# 11-DSP_PROCESSOR_1-OF-3.net
KiCad netlist of a schematic drawn in Altium Designer
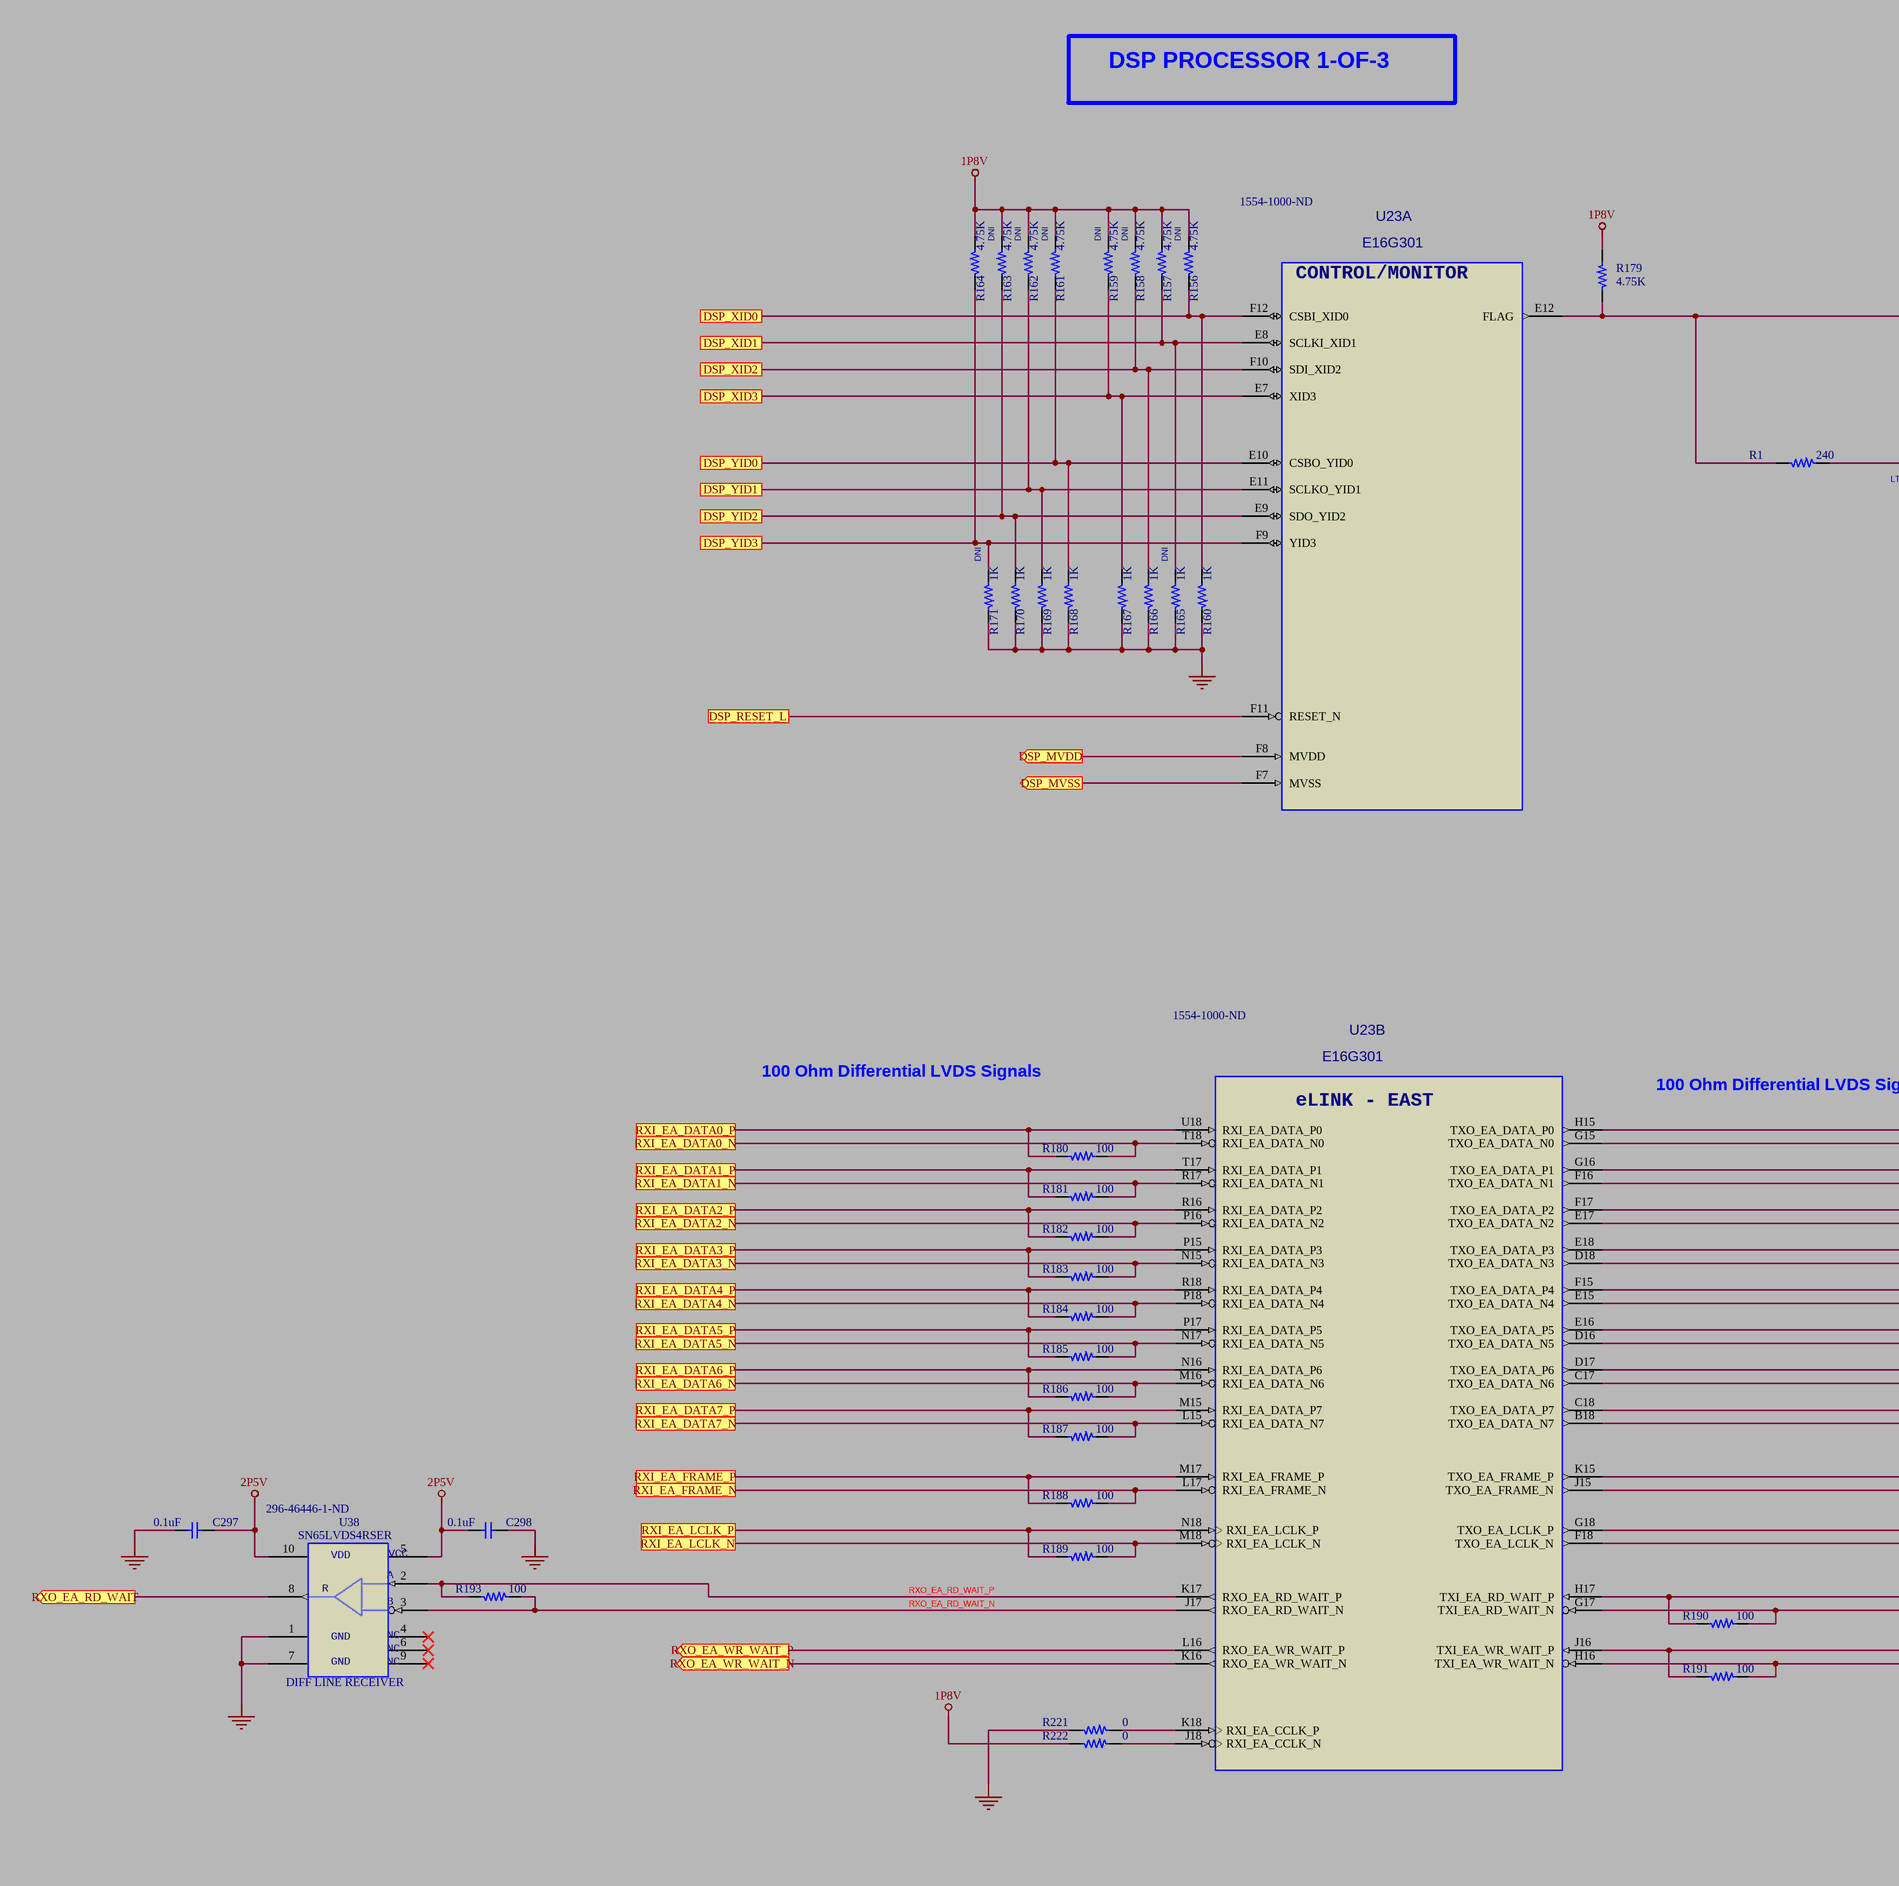
[diagram p0: 11-DSP PROCESSOR 1-OF-3.SchDoc, left]
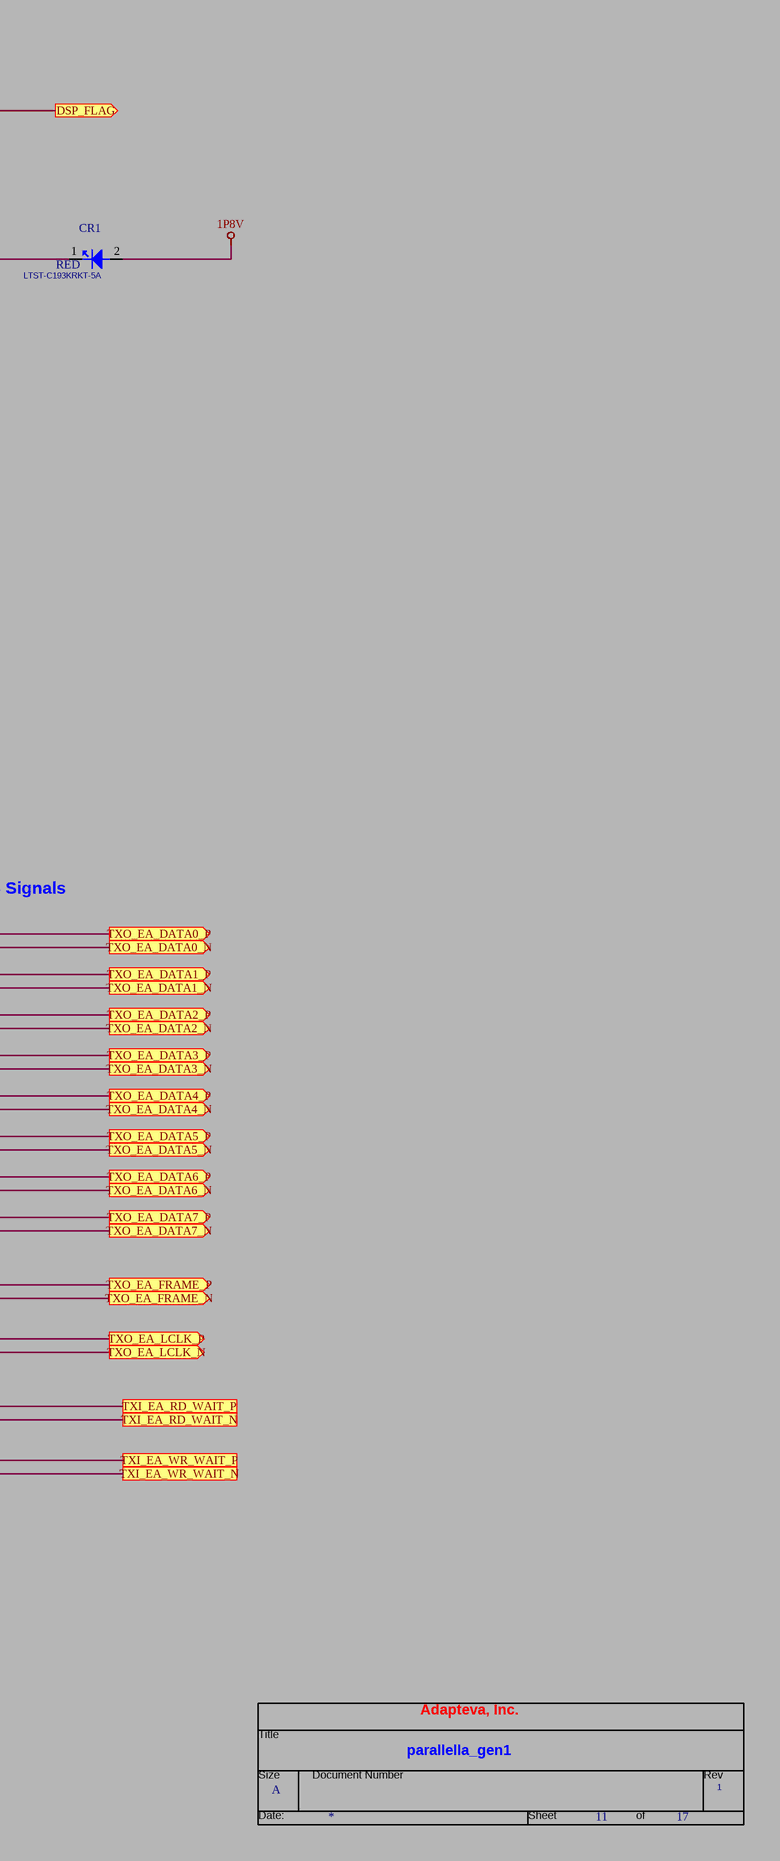
[diagram p1: 11-DSP PROCESSOR 1-OF-3.SchDoc, right]

(export (version "E")
  (design (tool "Eeschema 10.0.6"))
  (components
    (comp (ref "C297")
      (value "0.1uF")
      (footprint "C0402")
      (description "CAP, 0402, 0.1UF, X5R, 35V")
      (fields (field (name "MFG PART NO") "GMK105BJ104KV-F") (field (name "MFG") "TAIYO YUDEN"))
      (libsource (lib "*") (part "CAP0402_0P1UF_X5R_35V"))
    )
    (comp (ref "C298")
      (value "0.1uF")
      (footprint "C0402")
      (description "CAP, 0402, 0.1UF, X5R, 35V")
      (fields (field (name "MFG PART NO") "GMK105BJ104KV-F") (field (name "MFG") "TAIYO YUDEN"))
      (libsource (lib "*") (part "CAP0402_0P1UF_X5R_35V"))
    )
    (comp (ref "CR1")
      (value "RED")
      (footprint "LED_0603")
      (description "LED, 0603, 5MA, SMT, RED")
      (fields
        (field (name "VOLTAGE") "2V")
        (field (name "MFG") "LITE-ON INC")
        (field (name "VENDOR PN") "LTST-C193KRKT-5A")
      )
      (libsource (lib "*") (part "LED_0603_5MA_RED"))
    )
    (comp (ref "R1")
      (value "240")
      (footprint "R0402")
      (description "RES, 0402, 240, 1%")
      (fields (field (name "MFG") "VISHAY") (field (name "MFG PART NO") "CRCW0402240RFKED"))
      (libsource (lib "*") (part "RES0402_240"))
    )
    (comp (ref "R156")
      (value "4.75K")
      (footprint "R0402")
      (description "RES, 0402, 4.75K, 1%")
      (fields
        (field (name "MFG") "VISHAY")
        (field (name "MFG PART NO") "CRCW04024K75FKED")
        (field (name "INSTALL") "DNI")
      )
      (libsource (lib "*") (part "RES0402_4K75"))
    )
    (comp (ref "R157")
      (value "4.75K")
      (footprint "R0402")
      (description "RES, 0402, 4.75K, 1%")
      (fields (field (name "MFG") "VISHAY") (field (name "MFG PART NO") "CRCW04024K75FKED"))
      (libsource (lib "*") (part "RES0402_4K75"))
    )
    (comp (ref "R158")
      (value "4.75K")
      (footprint "R0402")
      (description "RES, 0402, 4.75K, 1%")
      (fields
        (field (name "MFG") "VISHAY")
        (field (name "MFG PART NO") "CRCW04024K75FKED")
        (field (name "INSTALL") "DNI")
      )
      (libsource (lib "*") (part "RES0402_4K75"))
    )
    (comp (ref "R159")
      (value "4.75K")
      (footprint "R0402")
      (description "RES, 0402, 4.75K, 1%")
      (fields
        (field (name "MFG") "VISHAY")
        (field (name "MFG PART NO") "CRCW04024K75FKED")
        (field (name "INSTALL") "DNI")
      )
      (libsource (lib "*") (part "RES0402_4K75"))
    )
    (comp (ref "R160")
      (value "1K")
      (footprint "R0402")
      (description "RES, 0402, 1K")
      (fields (field (name "MFG") "VISHAY") (field (name "MFG PART NO") "CRCW04021K00FKED"))
      (libsource (lib "*") (part "RES0402_1K"))
    )
    (comp (ref "R161")
      (value "4.75K")
      (footprint "R0402")
      (description "RES, 0402, 4.75K, 1%")
      (fields
        (field (name "MFG") "VISHAY")
        (field (name "MFG PART NO") "CRCW04024K75FKED")
        (field (name "INSTALL") "DNI")
      )
      (libsource (lib "*") (part "RES0402_4K75"))
    )
    (comp (ref "R162")
      (value "4.75K")
      (footprint "R0402")
      (description "RES, 0402, 4.75K, 1%")
      (fields
        (field (name "MFG") "VISHAY")
        (field (name "MFG PART NO") "CRCW04024K75FKED")
        (field (name "INSTALL") "DNI")
      )
      (libsource (lib "*") (part "RES0402_4K75"))
    )
    (comp (ref "R163")
      (value "4.75K")
      (footprint "R0402")
      (description "RES, 0402, 4.75K, 1%")
      (fields
        (field (name "MFG") "VISHAY")
        (field (name "MFG PART NO") "CRCW04024K75FKED")
        (field (name "INSTALL") "DNI")
      )
      (libsource (lib "*") (part "RES0402_4K75"))
    )
    (comp (ref "R164")
      (value "4.75K")
      (footprint "R0402")
      (description "RES, 0402, 4.75K, 1%")
      (fields (field (name "MFG") "VISHAY") (field (name "MFG PART NO") "CRCW04024K75FKED"))
      (libsource (lib "*") (part "RES0402_4K75"))
    )
    (comp (ref "R165")
      (value "1K")
      (footprint "R0402")
      (description "RES, 0402, 1K")
      (fields
        (field (name "MFG") "VISHAY")
        (field (name "MFG PART NO") "CRCW04021K00FKED")
        (field (name "INSTALL") "DNI")
      )
      (libsource (lib "*") (part "RES0402_1K"))
    )
    (comp (ref "R166")
      (value "1K")
      (footprint "R0402")
      (description "RES, 0402, 1K")
      (fields (field (name "MFG") "VISHAY") (field (name "MFG PART NO") "CRCW04021K00FKED"))
      (libsource (lib "*") (part "RES0402_1K"))
    )
    (comp (ref "R167")
      (value "1K")
      (footprint "R0402")
      (description "RES, 0402, 1K")
      (fields (field (name "MFG") "VISHAY") (field (name "MFG PART NO") "CRCW04021K00FKED"))
      (libsource (lib "*") (part "RES0402_1K"))
    )
    (comp (ref "R168")
      (value "1K")
      (footprint "R0402")
      (description "RES, 0402, 1K")
      (fields (field (name "MFG") "VISHAY") (field (name "MFG PART NO") "CRCW04021K00FKED"))
      (libsource (lib "*") (part "RES0402_1K"))
    )
    (comp (ref "R169")
      (value "1K")
      (footprint "R0402")
      (description "RES, 0402, 1K")
      (fields (field (name "MFG") "VISHAY") (field (name "MFG PART NO") "CRCW04021K00FKED"))
      (libsource (lib "*") (part "RES0402_1K"))
    )
    (comp (ref "R170")
      (value "1K")
      (footprint "R0402")
      (description "RES, 0402, 1K")
      (fields (field (name "MFG") "VISHAY") (field (name "MFG PART NO") "CRCW04021K00FKED"))
      (libsource (lib "*") (part "RES0402_1K"))
    )
    (comp (ref "R171")
      (value "1K")
      (footprint "R0402")
      (description "RES, 0402, 1K")
      (fields
        (field (name "MFG") "VISHAY")
        (field (name "MFG PART NO") "CRCW04021K00FKED")
        (field (name "INSTALL") "DNI")
      )
      (libsource (lib "*") (part "RES0402_1K"))
    )
    (comp (ref "R179")
      (value "4.75K")
      (footprint "R0402")
      (description "RES, 0402, 4.75K, 1%")
      (fields (field (name "MFG") "VISHAY") (field (name "MFG PART NO") "CRCW04024K75FKED"))
      (libsource (lib "*") (part "RES0402_4K75"))
    )
    (comp (ref "R180")
      (value "100")
      (footprint "R0402")
      (description "RES, 0402, 100, 1%")
      (fields (field (name "MFG PART NO") "CRCW0402100RFKED") (field (name "MFG") "VISHAY"))
      (libsource (lib "*") (part "RES0402_100"))
    )
    (comp (ref "R181")
      (value "100")
      (footprint "R0402")
      (description "RES, 0402, 100, 1%")
      (fields (field (name "MFG PART NO") "CRCW0402100RFKED") (field (name "MFG") "VISHAY"))
      (libsource (lib "*") (part "RES0402_100"))
    )
    (comp (ref "R182")
      (value "100")
      (footprint "R0402")
      (description "RES, 0402, 100, 1%")
      (fields (field (name "MFG PART NO") "CRCW0402100RFKED") (field (name "MFG") "VISHAY"))
      (libsource (lib "*") (part "RES0402_100"))
    )
    (comp (ref "R183")
      (value "100")
      (footprint "R0402")
      (description "RES, 0402, 100, 1%")
      (fields (field (name "MFG PART NO") "CRCW0402100RFKED") (field (name "MFG") "VISHAY"))
      (libsource (lib "*") (part "RES0402_100"))
    )
    (comp (ref "R184")
      (value "100")
      (footprint "R0402")
      (description "RES, 0402, 100, 1%")
      (fields (field (name "MFG PART NO") "CRCW0402100RFKED") (field (name "MFG") "VISHAY"))
      (libsource (lib "*") (part "RES0402_100"))
    )
    (comp (ref "R185")
      (value "100")
      (footprint "R0402")
      (description "RES, 0402, 100, 1%")
      (fields (field (name "MFG PART NO") "CRCW0402100RFKED") (field (name "MFG") "VISHAY"))
      (libsource (lib "*") (part "RES0402_100"))
    )
    (comp (ref "R186")
      (value "100")
      (footprint "R0402")
      (description "RES, 0402, 100, 1%")
      (fields (field (name "MFG PART NO") "CRCW0402100RFKED") (field (name "MFG") "VISHAY"))
      (libsource (lib "*") (part "RES0402_100"))
    )
    (comp (ref "R187")
      (value "100")
      (footprint "R0402")
      (description "RES, 0402, 100, 1%")
      (fields (field (name "MFG PART NO") "CRCW0402100RFKED") (field (name "MFG") "VISHAY"))
      (libsource (lib "*") (part "RES0402_100"))
    )
    (comp (ref "R188")
      (value "100")
      (footprint "R0402")
      (description "RES, 0402, 100, 1%")
      (fields (field (name "MFG PART NO") "CRCW0402100RFKED") (field (name "MFG") "VISHAY"))
      (libsource (lib "*") (part "RES0402_100"))
    )
    (comp (ref "R189")
      (value "100")
      (footprint "R0402")
      (description "RES, 0402, 100, 1%")
      (fields (field (name "MFG PART NO") "CRCW0402100RFKED") (field (name "MFG") "VISHAY"))
      (libsource (lib "*") (part "RES0402_100"))
    )
    (comp (ref "R190")
      (value "100")
      (footprint "R0402")
      (description "RES, 0402, 100, 1%")
      (fields (field (name "MFG PART NO") "CRCW0402100RFKED") (field (name "MFG") "VISHAY"))
      (libsource (lib "*") (part "RES0402_100"))
    )
    (comp (ref "R191")
      (value "100")
      (footprint "R0402")
      (description "RES, 0402, 100, 1%")
      (fields (field (name "MFG PART NO") "CRCW0402100RFKED") (field (name "MFG") "VISHAY"))
      (libsource (lib "*") (part "RES0402_100"))
    )
    (comp (ref "R193")
      (value "100")
      (footprint "R0402")
      (description "RES, 0402, 100, 1%")
      (fields (field (name "MFG PART NO") "CRCW0402100RFKED") (field (name "MFG") "VISHAY"))
      (libsource (lib "*") (part "RES0402_100"))
    )
    (comp (ref "R221")
      (value "0")
      (footprint "R0402")
      (description "RES, 0402, 0 OHM, 1%")
      (fields (field (name "MFG") "VISHAY") (field (name "MFG PART NO") "CRCW04020000Z0ED"))
      (libsource (lib "*") (part "RES0402_0"))
    )
    (comp (ref "R222")
      (value "0")
      (footprint "R0402")
      (description "RES, 0402, 0 OHM, 1%")
      (fields (field (name "MFG") "VISHAY") (field (name "MFG PART NO") "CRCW04020000Z0ED"))
      (libsource (lib "*") (part "RES0402_0"))
    )
    (comp (ref "U23")
      (value "16-CORE MICROPROCESSOR")
      (footprint "BGA324_15SQX1P5_P8MMP")
      (description "IC, 16-CORE MICROPROCESSOR, ADAPTEVA, E16G301, BGA324")
      (fields (field (name "VENDOR PN") "E16G301") (field (name "SUPPLIER PART NUMBER 1") "1554-1000-ND"))
      (libsource (lib "*") (part "EPIPHANY_E16G301"))
    )
    (comp (ref "U38")
      (value "DIFF LINE RECEIVER")
      (footprint "QFN-10_1P55X2P05XP6XP5MMP")
      (description "IC, LINE RECEIVER, DIFFERENTIAL LVDS, UFQFN10")
      (fields
        (field (name "VENDOR PN") "SN65LVDS4RSER")
        (field (name "MFG") "TEXAS INSTRUMENTS")
        (field (name "MFG PART NO") "SN65LVDS4RSER")
        (field (name "SUPPLIER PART NUMBER 1") "296-46446-1-ND")
      )
      (libsource (lib "*") (part "SN65LVDS4"))
    )
  )
  (nets
    (net (code "1") (name "/DSP_FLAG") (class "Default")
      (node (ref "R1") (pin "1") (pinfunction "1_1") (pintype "passive"))
      (node (ref "R179") (pin "1") (pinfunction "1_1") (pintype "passive"))
      (node (ref "U23") (pin "E12") (pinfunction "FLAG_E12") (pintype "output"))
    )
    (net (code "2") (name "/DSP_MVDD") (class "Default")
      (node (ref "U23") (pin "F8") (pinfunction "MVDD_F8") (pintype "input"))
    )
    (net (code "3") (name "/DSP_MVSS") (class "Default")
      (node (ref "U23") (pin "F7") (pinfunction "MVSS_F7") (pintype "input"))
    )
    (net (code "4") (name "/DSP_RESET_L") (class "Default")
      (node (ref "U23") (pin "F11") (pinfunction "RESET_N_F11") (pintype "input"))
    )
    (net (code "5") (name "/DSP_XID0") (class "Default")
      (node (ref "R156") (pin "1") (pinfunction "1_1") (pintype "passive"))
      (node (ref "R160") (pin "1") (pinfunction "1_1") (pintype "passive"))
      (node (ref "U23") (pin "F12") (pinfunction "CSBI_XID0_F12") (pintype "bidirectional"))
    )
    (net (code "6") (name "/DSP_XID1") (class "Default")
      (node (ref "R157") (pin "1") (pinfunction "1_1") (pintype "passive"))
      (node (ref "R165") (pin "1") (pinfunction "1_1") (pintype "passive"))
      (node (ref "U23") (pin "E8") (pinfunction "SCLKI_XID1_E8") (pintype "bidirectional"))
    )
    (net (code "7") (name "/DSP_XID2") (class "Default")
      (node (ref "R158") (pin "1") (pinfunction "1_1") (pintype "passive"))
      (node (ref "R166") (pin "1") (pinfunction "1_1") (pintype "passive"))
      (node (ref "U23") (pin "F10") (pinfunction "SDI_XID2_F10") (pintype "bidirectional"))
    )
    (net (code "8") (name "/DSP_XID3") (class "Default")
      (node (ref "R159") (pin "1") (pinfunction "1_1") (pintype "passive"))
      (node (ref "R167") (pin "1") (pinfunction "1_1") (pintype "passive"))
      (node (ref "U23") (pin "E7") (pinfunction "XID3_E7") (pintype "bidirectional"))
    )
    (net (code "9") (name "/DSP_YID0") (class "Default")
      (node (ref "R161") (pin "1") (pinfunction "1_1") (pintype "passive"))
      (node (ref "R168") (pin "1") (pinfunction "1_1") (pintype "passive"))
      (node (ref "U23") (pin "E10") (pinfunction "CSBO_YID0_E10") (pintype "bidirectional"))
    )
    (net (code "10") (name "/DSP_YID1") (class "Default")
      (node (ref "R162") (pin "1") (pinfunction "1_1") (pintype "passive"))
      (node (ref "R169") (pin "1") (pinfunction "1_1") (pintype "passive"))
      (node (ref "U23") (pin "E11") (pinfunction "SCLKO_YID1_E11") (pintype "bidirectional"))
    )
    (net (code "11") (name "/DSP_YID2") (class "Default")
      (node (ref "R163") (pin "1") (pinfunction "1_1") (pintype "passive"))
      (node (ref "R170") (pin "1") (pinfunction "1_1") (pintype "passive"))
      (node (ref "U23") (pin "E9") (pinfunction "SDO_YID2_E9") (pintype "bidirectional"))
    )
    (net (code "12") (name "/DSP_YID3") (class "Default")
      (node (ref "R164") (pin "1") (pinfunction "1_1") (pintype "passive"))
      (node (ref "R171") (pin "1") (pinfunction "1_1") (pintype "passive"))
      (node (ref "U23") (pin "F9") (pinfunction "YID3_F9") (pintype "bidirectional"))
    )
    (net (code "13") (name "/RXI_EA_DATA0_N") (class "Default")
      (node (ref "R180") (pin "2") (pinfunction "2_2") (pintype "passive"))
      (node (ref "U23") (pin "T18") (pinfunction "RXI_EA_DATA_N0_T18") (pintype "input"))
    )
    (net (code "14") (name "/RXI_EA_DATA0_P") (class "Default")
      (node (ref "R180") (pin "1") (pinfunction "1_1") (pintype "passive"))
      (node (ref "U23") (pin "U18") (pinfunction "RXI_EA_DATA_P0_U18") (pintype "input"))
    )
    (net (code "15") (name "/RXI_EA_DATA1_N") (class "Default")
      (node (ref "R181") (pin "2") (pinfunction "2_2") (pintype "passive"))
      (node (ref "U23") (pin "R17") (pinfunction "RXI_EA_DATA_N1_R17") (pintype "input"))
    )
    (net (code "16") (name "/RXI_EA_DATA1_P") (class "Default")
      (node (ref "R181") (pin "1") (pinfunction "1_1") (pintype "passive"))
      (node (ref "U23") (pin "T17") (pinfunction "RXI_EA_DATA_P1_T17") (pintype "input"))
    )
    (net (code "17") (name "/RXI_EA_DATA2_N") (class "Default")
      (node (ref "R182") (pin "2") (pinfunction "2_2") (pintype "passive"))
      (node (ref "U23") (pin "P16") (pinfunction "RXI_EA_DATA_N2_P16") (pintype "input"))
    )
    (net (code "18") (name "/RXI_EA_DATA2_P") (class "Default")
      (node (ref "R182") (pin "1") (pinfunction "1_1") (pintype "passive"))
      (node (ref "U23") (pin "R16") (pinfunction "RXI_EA_DATA_P2_R16") (pintype "input"))
    )
    (net (code "19") (name "/RXI_EA_DATA3_N") (class "Default")
      (node (ref "R183") (pin "2") (pinfunction "2_2") (pintype "passive"))
      (node (ref "U23") (pin "N15") (pinfunction "RXI_EA_DATA_N3_N15") (pintype "input"))
    )
    (net (code "20") (name "/RXI_EA_DATA3_P") (class "Default")
      (node (ref "R183") (pin "1") (pinfunction "1_1") (pintype "passive"))
      (node (ref "U23") (pin "P15") (pinfunction "RXI_EA_DATA_P3_P15") (pintype "input"))
    )
    (net (code "21") (name "/RXI_EA_DATA4_N") (class "Default")
      (node (ref "R184") (pin "2") (pinfunction "2_2") (pintype "passive"))
      (node (ref "U23") (pin "P18") (pinfunction "RXI_EA_DATA_N4_P18") (pintype "input"))
    )
    (net (code "22") (name "/RXI_EA_DATA4_P") (class "Default")
      (node (ref "R184") (pin "1") (pinfunction "1_1") (pintype "passive"))
      (node (ref "U23") (pin "R18") (pinfunction "RXI_EA_DATA_P4_R18") (pintype "input"))
    )
    (net (code "23") (name "/RXI_EA_DATA5_N") (class "Default")
      (node (ref "R185") (pin "2") (pinfunction "2_2") (pintype "passive"))
      (node (ref "U23") (pin "N17") (pinfunction "RXI_EA_DATA_N5_N17") (pintype "input"))
    )
    (net (code "24") (name "/RXI_EA_DATA5_P") (class "Default")
      (node (ref "R185") (pin "1") (pinfunction "1_1") (pintype "passive"))
      (node (ref "U23") (pin "P17") (pinfunction "RXI_EA_DATA_P5_P17") (pintype "input"))
    )
    (net (code "25") (name "/RXI_EA_DATA6_N") (class "Default")
      (node (ref "R186") (pin "2") (pinfunction "2_2") (pintype "passive"))
      (node (ref "U23") (pin "M16") (pinfunction "RXI_EA_DATA_N6_M16") (pintype "input"))
    )
    (net (code "26") (name "/RXI_EA_DATA6_P") (class "Default")
      (node (ref "R186") (pin "1") (pinfunction "1_1") (pintype "passive"))
      (node (ref "U23") (pin "N16") (pinfunction "RXI_EA_DATA_P6_N16") (pintype "input"))
    )
    (net (code "27") (name "/RXI_EA_DATA7_N") (class "Default")
      (node (ref "R187") (pin "2") (pinfunction "2_2") (pintype "passive"))
      (node (ref "U23") (pin "L15") (pinfunction "RXI_EA_DATA_N7_L15") (pintype "input"))
    )
    (net (code "28") (name "/RXI_EA_DATA7_P") (class "Default")
      (node (ref "R187") (pin "1") (pinfunction "1_1") (pintype "passive"))
      (node (ref "U23") (pin "M15") (pinfunction "RXI_EA_DATA_P7_M15") (pintype "input"))
    )
    (net (code "29") (name "/RXI_EA_FRAME_N") (class "Default")
      (node (ref "R188") (pin "2") (pinfunction "2_2") (pintype "passive"))
      (node (ref "U23") (pin "L17") (pinfunction "RXI_EA_FRAME_N_L17") (pintype "input"))
    )
    (net (code "30") (name "/RXI_EA_FRAME_P") (class "Default")
      (node (ref "R188") (pin "1") (pinfunction "1_1") (pintype "passive"))
      (node (ref "U23") (pin "M17") (pinfunction "RXI_EA_FRAME_P_M17") (pintype "input"))
    )
    (net (code "31") (name "/RXI_EA_LCLK_N") (class "Default")
      (node (ref "R189") (pin "2") (pinfunction "2_2") (pintype "passive"))
      (node (ref "U23") (pin "M18") (pinfunction "RXI_EA_LCLK_N_M18") (pintype "input"))
    )
    (net (code "32") (name "/RXI_EA_LCLK_P") (class "Default")
      (node (ref "R189") (pin "1") (pinfunction "1_1") (pintype "passive"))
      (node (ref "U23") (pin "N18") (pinfunction "RXI_EA_LCLK_P_N18") (pintype "input"))
    )
    (net (code "33") (name "/RXO_EA_RD_WAIT") (class "Default")
      (node (ref "U38") (pin "8") (pinfunction "R_8") (pintype "output"))
    )
    (net (code "34") (name "/RXO_EA_RD_WAIT_N") (class "Default")
      (node (ref "R193") (pin "2") (pinfunction "2_2") (pintype "passive"))
      (node (ref "U23") (pin "J17") (pinfunction "RXO_EA_RD_WAIT_N_J17") (pintype "output"))
      (node (ref "U38") (pin "3") (pinfunction "B_3") (pintype "input"))
    )
    (net (code "35") (name "/RXO_EA_RD_WAIT_P") (class "Default")
      (node (ref "R193") (pin "1") (pinfunction "1_1") (pintype "passive"))
      (node (ref "U23") (pin "K17") (pinfunction "RXO_EA_RD_WAIT_P_K17") (pintype "output"))
      (node (ref "U38") (pin "2") (pinfunction "A_2") (pintype "input"))
    )
    (net (code "36") (name "/RXO_EA_WR_WAIT_N") (class "Default")
      (node (ref "U23") (pin "K16") (pinfunction "RXO_EA_WR_WAIT_N_K16") (pintype "output"))
    )
    (net (code "37") (name "/RXO_EA_WR_WAIT_P") (class "Default")
      (node (ref "U23") (pin "L16") (pinfunction "RXO_EA_WR_WAIT_P_L16") (pintype "output"))
    )
    (net (code "38") (name "/TXI_EA_RD_WAIT_N") (class "Default")
      (node (ref "R190") (pin "2") (pinfunction "2_2") (pintype "passive"))
      (node (ref "U23") (pin "G17") (pinfunction "TXI_EA_RD_WAIT_N_G17") (pintype "input"))
    )
    (net (code "39") (name "/TXI_EA_RD_WAIT_P") (class "Default")
      (node (ref "R190") (pin "1") (pinfunction "1_1") (pintype "passive"))
      (node (ref "U23") (pin "H17") (pinfunction "TXI_EA_RD_WAIT_P_H17") (pintype "input"))
    )
    (net (code "40") (name "/TXI_EA_WR_WAIT_N") (class "Default")
      (node (ref "R191") (pin "2") (pinfunction "2_2") (pintype "passive"))
      (node (ref "U23") (pin "H16") (pinfunction "TXI_EA_WR_WAIT_N_H16") (pintype "input"))
    )
    (net (code "41") (name "/TXI_EA_WR_WAIT_P") (class "Default")
      (node (ref "R191") (pin "1") (pinfunction "1_1") (pintype "passive"))
      (node (ref "U23") (pin "J16") (pinfunction "TXI_EA_WR_WAIT_P_J16") (pintype "input"))
    )
    (net (code "42") (name "/TXO_EA_DATA0_N") (class "Default")
      (node (ref "U23") (pin "G15") (pinfunction "TXO_EA_DATA_N0_G15") (pintype "output"))
    )
    (net (code "43") (name "/TXO_EA_DATA0_P") (class "Default")
      (node (ref "U23") (pin "H15") (pinfunction "TXO_EA_DATA_P0_H15") (pintype "output"))
    )
    (net (code "44") (name "/TXO_EA_DATA1_N") (class "Default")
      (node (ref "U23") (pin "F16") (pinfunction "TXO_EA_DATA_N1_F16") (pintype "output"))
    )
    (net (code "45") (name "/TXO_EA_DATA1_P") (class "Default")
      (node (ref "U23") (pin "G16") (pinfunction "TXO_EA_DATA_P1_G16") (pintype "output"))
    )
    (net (code "46") (name "/TXO_EA_DATA2_N") (class "Default")
      (node (ref "U23") (pin "E17") (pinfunction "TXO_EA_DATA_N2_E17") (pintype "output"))
    )
    (net (code "47") (name "/TXO_EA_DATA2_P") (class "Default")
      (node (ref "U23") (pin "F17") (pinfunction "TXO_EA_DATA_P2_F17") (pintype "output"))
    )
    (net (code "48") (name "/TXO_EA_DATA3_N") (class "Default")
      (node (ref "U23") (pin "D18") (pinfunction "TXO_EA_DATA_N3_D18") (pintype "output"))
    )
    (net (code "49") (name "/TXO_EA_DATA3_P") (class "Default")
      (node (ref "U23") (pin "E18") (pinfunction "TXO_EA_DATA_P3_E18") (pintype "output"))
    )
    (net (code "50") (name "/TXO_EA_DATA4_N") (class "Default")
      (node (ref "U23") (pin "E15") (pinfunction "TXO_EA_DATA_N4_E15") (pintype "output"))
    )
    (net (code "51") (name "/TXO_EA_DATA4_P") (class "Default")
      (node (ref "U23") (pin "F15") (pinfunction "TXO_EA_DATA_P4_F15") (pintype "output"))
    )
    (net (code "52") (name "/TXO_EA_DATA5_N") (class "Default")
      (node (ref "U23") (pin "D16") (pinfunction "TXO_EA_DATA_N5_D16") (pintype "output"))
    )
    (net (code "53") (name "/TXO_EA_DATA5_P") (class "Default")
      (node (ref "U23") (pin "E16") (pinfunction "TXO_EA_DATA_P5_E16") (pintype "output"))
    )
    (net (code "54") (name "/TXO_EA_DATA6_N") (class "Default")
      (node (ref "U23") (pin "C17") (pinfunction "TXO_EA_DATA_N6_C17") (pintype "output"))
    )
    (net (code "55") (name "/TXO_EA_DATA6_P") (class "Default")
      (node (ref "U23") (pin "D17") (pinfunction "TXO_EA_DATA_P6_D17") (pintype "output"))
    )
    (net (code "56") (name "/TXO_EA_DATA7_N") (class "Default")
      (node (ref "U23") (pin "B18") (pinfunction "TXO_EA_DATA_N7_B18") (pintype "output"))
    )
    (net (code "57") (name "/TXO_EA_DATA7_P") (class "Default")
      (node (ref "U23") (pin "C18") (pinfunction "TXO_EA_DATA_P7_C18") (pintype "output"))
    )
    (net (code "58") (name "/TXO_EA_FRAME_N") (class "Default")
      (node (ref "U23") (pin "J15") (pinfunction "TXO_EA_FRAME_N_J15") (pintype "output"))
    )
    (net (code "59") (name "/TXO_EA_FRAME_P") (class "Default")
      (node (ref "U23") (pin "K15") (pinfunction "TXO_EA_FRAME_P_K15") (pintype "output"))
    )
    (net (code "60") (name "/TXO_EA_LCLK_N") (class "Default")
      (node (ref "U23") (pin "F18") (pinfunction "TXO_EA_LCLK_N_F18") (pintype "output"))
    )
    (net (code "61") (name "/TXO_EA_LCLK_P") (class "Default")
      (node (ref "U23") (pin "G18") (pinfunction "TXO_EA_LCLK_P_G18") (pintype "output"))
    )
    (net (code "62") (name "1P8V") (class "Default")
      (node (ref "CR1") (pin "2") (pinfunction "A_2") (pintype "passive"))
      (node (ref "R156") (pin "2") (pinfunction "2_2") (pintype "passive"))
      (node (ref "R157") (pin "2") (pinfunction "2_2") (pintype "passive"))
      (node (ref "R158") (pin "2") (pinfunction "2_2") (pintype "passive"))
      (node (ref "R159") (pin "2") (pinfunction "2_2") (pintype "passive"))
      (node (ref "R161") (pin "2") (pinfunction "2_2") (pintype "passive"))
      (node (ref "R162") (pin "2") (pinfunction "2_2") (pintype "passive"))
      (node (ref "R163") (pin "2") (pinfunction "2_2") (pintype "passive"))
      (node (ref "R164") (pin "2") (pinfunction "2_2") (pintype "passive"))
      (node (ref "R179") (pin "2") (pinfunction "2_2") (pintype "passive"))
      (node (ref "R222") (pin "1") (pinfunction "1_1") (pintype "passive"))
    )
    (net (code "63") (name "2P5V") (class "Default")
      (node (ref "C297") (pin "2") (pinfunction "2_2") (pintype "passive"))
      (node (ref "C298") (pin "1") (pinfunction "1_1") (pintype "passive"))
      (node (ref "U38") (pin "10") (pinfunction "VDD_10") (pintype "power_in"))
      (node (ref "U38") (pin "5") (pinfunction "VCC_5") (pintype "power_in"))
    )
    (net (code "64") (name "GND") (class "Default")
      (node (ref "C297") (pin "1") (pinfunction "1_1") (pintype "passive"))
      (node (ref "C298") (pin "2") (pinfunction "2_2") (pintype "passive"))
      (node (ref "R160") (pin "2") (pinfunction "2_2") (pintype "passive"))
      (node (ref "R165") (pin "2") (pinfunction "2_2") (pintype "passive"))
      (node (ref "R166") (pin "2") (pinfunction "2_2") (pintype "passive"))
      (node (ref "R167") (pin "2") (pinfunction "2_2") (pintype "passive"))
      (node (ref "R168") (pin "2") (pinfunction "2_2") (pintype "passive"))
      (node (ref "R169") (pin "2") (pinfunction "2_2") (pintype "passive"))
      (node (ref "R170") (pin "2") (pinfunction "2_2") (pintype "passive"))
      (node (ref "R171") (pin "2") (pinfunction "2_2") (pintype "passive"))
      (node (ref "R221") (pin "1") (pinfunction "1_1") (pintype "passive"))
      (node (ref "U38") (pin "1") (pinfunction "GND1_1") (pintype "power_in"))
      (node (ref "U38") (pin "7") (pinfunction "GND2_7") (pintype "power_in"))
    )
    (net (code "65") (name "Net-(CR1-C)") (class "Default")
      (node (ref "CR1") (pin "1") (pinfunction "C_1") (pintype "passive"))
      (node (ref "R1") (pin "2") (pinfunction "2_2") (pintype "passive"))
    )
    (net (code "66") (name "Net-(U23B-RXI_EA_CCLK_N)") (class "Default")
      (node (ref "R222") (pin "2") (pinfunction "2_2") (pintype "passive"))
      (node (ref "U23") (pin "J18") (pinfunction "RXI_EA_CCLK_N_J18") (pintype "input"))
    )
    (net (code "67") (name "Net-(U23B-RXI_EA_CCLK_P)") (class "Default")
      (node (ref "R221") (pin "2") (pinfunction "2_2") (pintype "passive"))
      (node (ref "U23") (pin "K18") (pinfunction "RXI_EA_CCLK_P_K18") (pintype "input"))
    )
    (net (code "68") (name "unconnected-(U38-NC1-Pad4)") (class "Default")
      (node (ref "U38") (pin "4") (pinfunction "NC1_4") (pintype "passive+no_connect"))
    )
    (net (code "69") (name "unconnected-(U38-NC2-Pad6)") (class "Default")
      (node (ref "U38") (pin "6") (pinfunction "NC2_6") (pintype "passive+no_connect"))
    )
    (net (code "70") (name "unconnected-(U38-NC3-Pad9)") (class "Default")
      (node (ref "U38") (pin "9") (pinfunction "NC3_9") (pintype "passive+no_connect"))
    )
  )
)
